# DDB_Power_Supply.net
KiCad netlist of a schematic drawn in EAGLE
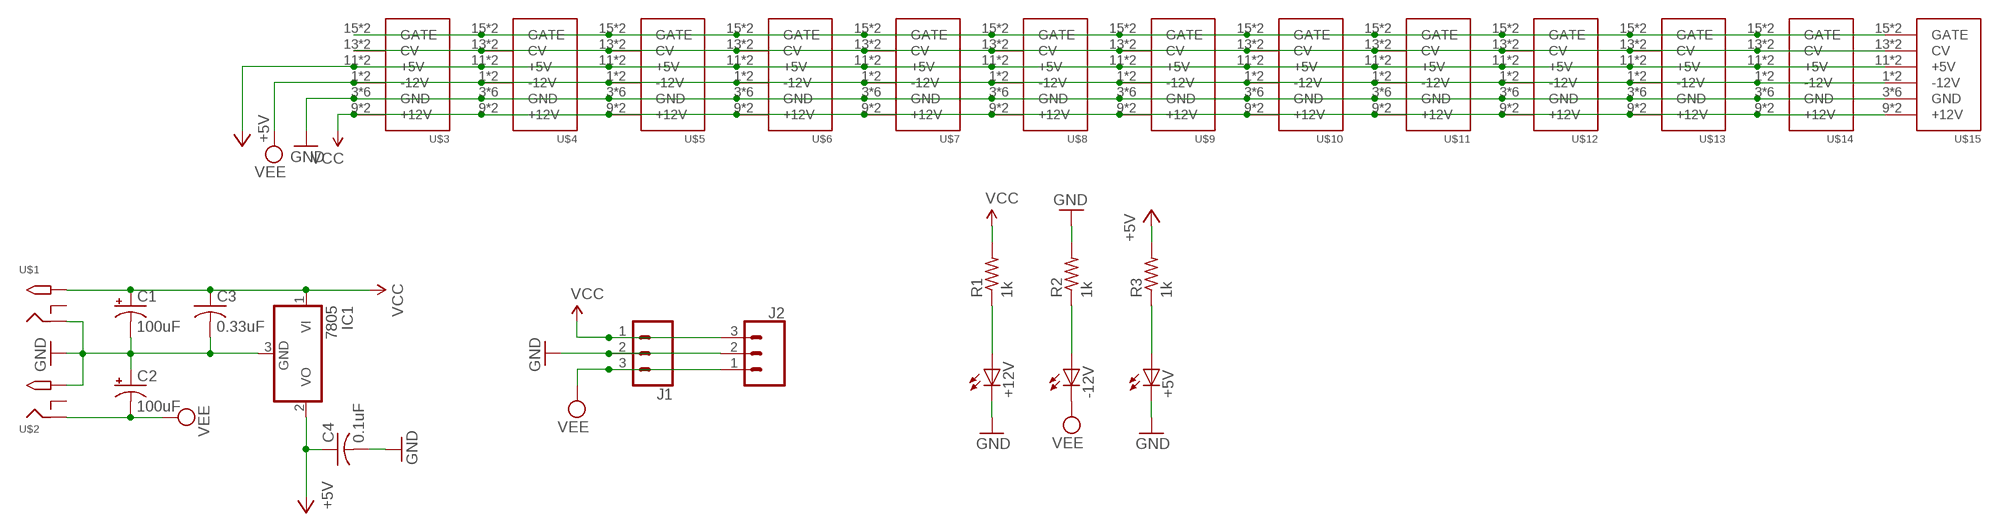
[diagram p0: schematic, sheet 1]

(export (version "E")
  (design (tool "Eeschema 10.0.6"))
  (components
    (comp (ref "+5V")
      (value "LED3MM")
      (footprint "eagle-import:LED3MM")
      (libsource (lib "eagle-import") (part "LED3MM"))
    )
    (comp (ref "+12V")
      (value "LED3MM")
      (footprint "eagle-import:LED3MM")
      (libsource (lib "eagle-import") (part "LED3MM"))
    )
    (comp (ref "-12V")
      (value "LED3MM")
      (footprint "eagle-import:LED3MM")
      (libsource (lib "eagle-import") (part "LED3MM"))
    )
    (comp (ref "C1")
      (value "100uF")
      (footprint "eagle-import:E3,5-8")
      (libsource (lib "eagle-import") (part "CPOL-USE3.5-8"))
    )
    (comp (ref "C2")
      (value "100uF")
      (footprint "eagle-import:E3,5-8")
      (libsource (lib "eagle-import") (part "CPOL-USE3.5-8"))
    )
    (comp (ref "C3")
      (value "0.33uF")
      (footprint "eagle-import:C0805")
      (libsource (lib "eagle-import") (part "C-USC0805"))
    )
    (comp (ref "C4")
      (value "0.1uF")
      (footprint "eagle-import:C0805")
      (libsource (lib "eagle-import") (part "C-USC0805"))
    )
    (comp (ref "IC1")
      (value "7805")
      (footprint "eagle-import:TO252")
      (libsource (lib "eagle-import") (part "78DT24"))
    )
    (comp (ref "J1")
      (value "CONN_03SCREW")
      (footprint "eagle-import:SCREWTERMINAL-3.5MM-3")
      (libsource (lib "eagle-import") (part "CONN_03SCREW"))
    )
    (comp (ref "J2")
      (value "CONN_03SCREW")
      (footprint "eagle-import:SCREWTERMINAL-3.5MM-3")
      (libsource (lib "eagle-import") (part "CONN_03SCREW"))
    )
    (comp (ref "R1")
      (value "1k")
      (footprint "eagle-import:R0805")
      (libsource (lib "eagle-import") (part "R-US_R0805"))
    )
    (comp (ref "R2")
      (value "1k")
      (footprint "eagle-import:R0805")
      (libsource (lib "eagle-import") (part "R-US_R0805"))
    )
    (comp (ref "R3")
      (value "1k")
      (footprint "eagle-import:R0805")
      (libsource (lib "eagle-import") (part "R-US_R0805"))
    )
    (comp (ref "U$1")
      (value "2.1MMJACKTHM")
      (footprint "eagle-import:PJ-102A")
      (libsource (lib "eagle-import") (part "2.1MMJACKTHM"))
    )
    (comp (ref "U$2")
      (value "2.1MMJACKTHM")
      (footprint "eagle-import:PJ-102A")
      (libsource (lib "eagle-import") (part "2.1MMJACKTHM"))
    )
    (comp (ref "U$3")
      (value "POWER")
      (footprint "eagle-import:POWER_16")
      (libsource (lib "eagle-import") (part "POWER"))
    )
    (comp (ref "U$4")
      (value "POWER")
      (footprint "eagle-import:POWER_16")
      (libsource (lib "eagle-import") (part "POWER"))
    )
    (comp (ref "U$5")
      (value "POWER")
      (footprint "eagle-import:POWER_16")
      (libsource (lib "eagle-import") (part "POWER"))
    )
    (comp (ref "U$6")
      (value "POWER")
      (footprint "eagle-import:POWER_16")
      (libsource (lib "eagle-import") (part "POWER"))
    )
    (comp (ref "U$7")
      (value "POWER")
      (footprint "eagle-import:POWER_16")
      (libsource (lib "eagle-import") (part "POWER"))
    )
    (comp (ref "U$8")
      (value "POWER")
      (footprint "eagle-import:POWER_16")
      (libsource (lib "eagle-import") (part "POWER"))
    )
    (comp (ref "U$9")
      (value "POWER")
      (footprint "eagle-import:POWER_16")
      (libsource (lib "eagle-import") (part "POWER"))
    )
    (comp (ref "U$10")
      (value "POWER")
      (footprint "eagle-import:POWER_16")
      (libsource (lib "eagle-import") (part "POWER"))
    )
    (comp (ref "U$11")
      (value "POWER")
      (footprint "eagle-import:POWER_16")
      (libsource (lib "eagle-import") (part "POWER"))
    )
    (comp (ref "U$12")
      (value "POWER")
      (footprint "eagle-import:POWER_16")
      (libsource (lib "eagle-import") (part "POWER"))
    )
    (comp (ref "U$13")
      (value "POWER")
      (footprint "eagle-import:POWER_16")
      (libsource (lib "eagle-import") (part "POWER"))
    )
    (comp (ref "U$14")
      (value "POWER")
      (footprint "eagle-import:POWER_16")
      (libsource (lib "eagle-import") (part "POWER"))
    )
    (comp (ref "U$15")
      (value "POWER")
      (footprint "eagle-import:POWER_16")
      (libsource (lib "eagle-import") (part "POWER"))
    )
  )
  (nets
    (net (code "1") (name "+5V") (class "Default")
      (node (ref "C4") (pin "1") (pinfunction "1_1") (pintype "passive"))
      (node (ref "IC1") (pin "2") (pinfunction "VO_2") (pintype "passive"))
      (node (ref "R3") (pin "2") (pinfunction "2_2") (pintype "passive"))
      (node (ref "U$10") (pin "11") (pinfunction "+5V_11") (pintype "bidirectional"))
      (node (ref "U$10") (pin "12") (pinfunction "+5V_12") (pintype "bidirectional"))
      (node (ref "U$11") (pin "11") (pinfunction "+5V_11") (pintype "bidirectional"))
      (node (ref "U$11") (pin "12") (pinfunction "+5V_12") (pintype "bidirectional"))
      (node (ref "U$12") (pin "11") (pinfunction "+5V_11") (pintype "bidirectional"))
      (node (ref "U$12") (pin "12") (pinfunction "+5V_12") (pintype "bidirectional"))
      (node (ref "U$13") (pin "11") (pinfunction "+5V_11") (pintype "bidirectional"))
      (node (ref "U$13") (pin "12") (pinfunction "+5V_12") (pintype "bidirectional"))
      (node (ref "U$14") (pin "11") (pinfunction "+5V_11") (pintype "bidirectional"))
      (node (ref "U$14") (pin "12") (pinfunction "+5V_12") (pintype "bidirectional"))
      (node (ref "U$15") (pin "11") (pinfunction "+5V_11") (pintype "bidirectional"))
      (node (ref "U$15") (pin "12") (pinfunction "+5V_12") (pintype "bidirectional"))
      (node (ref "U$3") (pin "11") (pinfunction "+5V_11") (pintype "bidirectional"))
      (node (ref "U$3") (pin "12") (pinfunction "+5V_12") (pintype "bidirectional"))
      (node (ref "U$4") (pin "11") (pinfunction "+5V_11") (pintype "bidirectional"))
      (node (ref "U$4") (pin "12") (pinfunction "+5V_12") (pintype "bidirectional"))
      (node (ref "U$5") (pin "11") (pinfunction "+5V_11") (pintype "bidirectional"))
      (node (ref "U$5") (pin "12") (pinfunction "+5V_12") (pintype "bidirectional"))
      (node (ref "U$6") (pin "11") (pinfunction "+5V_11") (pintype "bidirectional"))
      (node (ref "U$6") (pin "12") (pinfunction "+5V_12") (pintype "bidirectional"))
      (node (ref "U$7") (pin "11") (pinfunction "+5V_11") (pintype "bidirectional"))
      (node (ref "U$7") (pin "12") (pinfunction "+5V_12") (pintype "bidirectional"))
      (node (ref "U$8") (pin "11") (pinfunction "+5V_11") (pintype "bidirectional"))
      (node (ref "U$8") (pin "12") (pinfunction "+5V_12") (pintype "bidirectional"))
      (node (ref "U$9") (pin "11") (pinfunction "+5V_11") (pintype "bidirectional"))
      (node (ref "U$9") (pin "12") (pinfunction "+5V_12") (pintype "bidirectional"))
    )
    (net (code "2") (name "GND") (class "Default")
      (node (ref "+12V") (pin "K") (pinfunction "C_K") (pintype "passive"))
      (node (ref "+5V") (pin "K") (pinfunction "C_K") (pintype "passive"))
      (node (ref "C1") (pin "-") (pinfunction "-_-") (pintype "passive"))
      (node (ref "C2") (pin "+") (pinfunction "+_+") (pintype "passive"))
      (node (ref "C3") (pin "2") (pinfunction "2_2") (pintype "passive"))
      (node (ref "C4") (pin "2") (pinfunction "2_2") (pintype "passive"))
      (node (ref "IC1") (pin "3") (pinfunction "GND_3") (pintype "passive"))
      (node (ref "J1") (pin "2") (pinfunction "2_2") (pintype "passive"))
      (node (ref "J2") (pin "2") (pinfunction "2_2") (pintype "passive"))
      (node (ref "R2") (pin "2") (pinfunction "2_2") (pintype "passive"))
      (node (ref "U$1") (pin "RING") (pinfunction "RING_RING") (pintype "bidirectional"))
      (node (ref "U$10") (pin "3") (pinfunction "GND_3") (pintype "bidirectional"))
      (node (ref "U$10") (pin "4") (pinfunction "GND_4") (pintype "bidirectional"))
      (node (ref "U$10") (pin "5") (pinfunction "GND_5") (pintype "bidirectional"))
      (node (ref "U$10") (pin "6") (pinfunction "GND_6") (pintype "bidirectional"))
      (node (ref "U$10") (pin "7") (pinfunction "GND_7") (pintype "bidirectional"))
      (node (ref "U$10") (pin "8") (pinfunction "GND_8") (pintype "bidirectional"))
      (node (ref "U$11") (pin "3") (pinfunction "GND_3") (pintype "bidirectional"))
      (node (ref "U$11") (pin "4") (pinfunction "GND_4") (pintype "bidirectional"))
      (node (ref "U$11") (pin "5") (pinfunction "GND_5") (pintype "bidirectional"))
      (node (ref "U$11") (pin "6") (pinfunction "GND_6") (pintype "bidirectional"))
      (node (ref "U$11") (pin "7") (pinfunction "GND_7") (pintype "bidirectional"))
      (node (ref "U$11") (pin "8") (pinfunction "GND_8") (pintype "bidirectional"))
      (node (ref "U$12") (pin "3") (pinfunction "GND_3") (pintype "bidirectional"))
      (node (ref "U$12") (pin "4") (pinfunction "GND_4") (pintype "bidirectional"))
      (node (ref "U$12") (pin "5") (pinfunction "GND_5") (pintype "bidirectional"))
      (node (ref "U$12") (pin "6") (pinfunction "GND_6") (pintype "bidirectional"))
      (node (ref "U$12") (pin "7") (pinfunction "GND_7") (pintype "bidirectional"))
      (node (ref "U$12") (pin "8") (pinfunction "GND_8") (pintype "bidirectional"))
      (node (ref "U$13") (pin "3") (pinfunction "GND_3") (pintype "bidirectional"))
      (node (ref "U$13") (pin "4") (pinfunction "GND_4") (pintype "bidirectional"))
      (node (ref "U$13") (pin "5") (pinfunction "GND_5") (pintype "bidirectional"))
      (node (ref "U$13") (pin "6") (pinfunction "GND_6") (pintype "bidirectional"))
      (node (ref "U$13") (pin "7") (pinfunction "GND_7") (pintype "bidirectional"))
      (node (ref "U$13") (pin "8") (pinfunction "GND_8") (pintype "bidirectional"))
      (node (ref "U$14") (pin "3") (pinfunction "GND_3") (pintype "bidirectional"))
      (node (ref "U$14") (pin "4") (pinfunction "GND_4") (pintype "bidirectional"))
      (node (ref "U$14") (pin "5") (pinfunction "GND_5") (pintype "bidirectional"))
      (node (ref "U$14") (pin "6") (pinfunction "GND_6") (pintype "bidirectional"))
      (node (ref "U$14") (pin "7") (pinfunction "GND_7") (pintype "bidirectional"))
      (node (ref "U$14") (pin "8") (pinfunction "GND_8") (pintype "bidirectional"))
      (node (ref "U$15") (pin "3") (pinfunction "GND_3") (pintype "bidirectional"))
      (node (ref "U$15") (pin "4") (pinfunction "GND_4") (pintype "bidirectional"))
      (node (ref "U$15") (pin "5") (pinfunction "GND_5") (pintype "bidirectional"))
      (node (ref "U$15") (pin "6") (pinfunction "GND_6") (pintype "bidirectional"))
      (node (ref "U$15") (pin "7") (pinfunction "GND_7") (pintype "bidirectional"))
      (node (ref "U$15") (pin "8") (pinfunction "GND_8") (pintype "bidirectional"))
      (node (ref "U$2") (pin "TIP") (pinfunction "TIP_TIP") (pintype "bidirectional"))
      (node (ref "U$3") (pin "3") (pinfunction "GND_3") (pintype "bidirectional"))
      (node (ref "U$3") (pin "4") (pinfunction "GND_4") (pintype "bidirectional"))
      (node (ref "U$3") (pin "5") (pinfunction "GND_5") (pintype "bidirectional"))
      (node (ref "U$3") (pin "6") (pinfunction "GND_6") (pintype "bidirectional"))
      (node (ref "U$3") (pin "7") (pinfunction "GND_7") (pintype "bidirectional"))
      (node (ref "U$3") (pin "8") (pinfunction "GND_8") (pintype "bidirectional"))
      (node (ref "U$4") (pin "3") (pinfunction "GND_3") (pintype "bidirectional"))
      (node (ref "U$4") (pin "4") (pinfunction "GND_4") (pintype "bidirectional"))
      (node (ref "U$4") (pin "5") (pinfunction "GND_5") (pintype "bidirectional"))
      (node (ref "U$4") (pin "6") (pinfunction "GND_6") (pintype "bidirectional"))
      (node (ref "U$4") (pin "7") (pinfunction "GND_7") (pintype "bidirectional"))
      (node (ref "U$4") (pin "8") (pinfunction "GND_8") (pintype "bidirectional"))
      (node (ref "U$5") (pin "3") (pinfunction "GND_3") (pintype "bidirectional"))
      (node (ref "U$5") (pin "4") (pinfunction "GND_4") (pintype "bidirectional"))
      (node (ref "U$5") (pin "5") (pinfunction "GND_5") (pintype "bidirectional"))
      (node (ref "U$5") (pin "6") (pinfunction "GND_6") (pintype "bidirectional"))
      (node (ref "U$5") (pin "7") (pinfunction "GND_7") (pintype "bidirectional"))
      (node (ref "U$5") (pin "8") (pinfunction "GND_8") (pintype "bidirectional"))
      (node (ref "U$6") (pin "3") (pinfunction "GND_3") (pintype "bidirectional"))
      (node (ref "U$6") (pin "4") (pinfunction "GND_4") (pintype "bidirectional"))
      (node (ref "U$6") (pin "5") (pinfunction "GND_5") (pintype "bidirectional"))
      (node (ref "U$6") (pin "6") (pinfunction "GND_6") (pintype "bidirectional"))
      (node (ref "U$6") (pin "7") (pinfunction "GND_7") (pintype "bidirectional"))
      (node (ref "U$6") (pin "8") (pinfunction "GND_8") (pintype "bidirectional"))
      (node (ref "U$7") (pin "3") (pinfunction "GND_3") (pintype "bidirectional"))
      (node (ref "U$7") (pin "4") (pinfunction "GND_4") (pintype "bidirectional"))
      (node (ref "U$7") (pin "5") (pinfunction "GND_5") (pintype "bidirectional"))
      (node (ref "U$7") (pin "6") (pinfunction "GND_6") (pintype "bidirectional"))
      (node (ref "U$7") (pin "7") (pinfunction "GND_7") (pintype "bidirectional"))
      (node (ref "U$7") (pin "8") (pinfunction "GND_8") (pintype "bidirectional"))
      (node (ref "U$8") (pin "3") (pinfunction "GND_3") (pintype "bidirectional"))
      (node (ref "U$8") (pin "4") (pinfunction "GND_4") (pintype "bidirectional"))
      (node (ref "U$8") (pin "5") (pinfunction "GND_5") (pintype "bidirectional"))
      (node (ref "U$8") (pin "6") (pinfunction "GND_6") (pintype "bidirectional"))
      (node (ref "U$8") (pin "7") (pinfunction "GND_7") (pintype "bidirectional"))
      (node (ref "U$8") (pin "8") (pinfunction "GND_8") (pintype "bidirectional"))
      (node (ref "U$9") (pin "3") (pinfunction "GND_3") (pintype "bidirectional"))
      (node (ref "U$9") (pin "4") (pinfunction "GND_4") (pintype "bidirectional"))
      (node (ref "U$9") (pin "5") (pinfunction "GND_5") (pintype "bidirectional"))
      (node (ref "U$9") (pin "6") (pinfunction "GND_6") (pintype "bidirectional"))
      (node (ref "U$9") (pin "7") (pinfunction "GND_7") (pintype "bidirectional"))
      (node (ref "U$9") (pin "8") (pinfunction "GND_8") (pintype "bidirectional"))
    )
    (net (code "3") (name "Net-(+5V-PadA)") (class "Default")
      (node (ref "+5V") (pin "A") (pinfunction "A_A") (pintype "passive"))
      (node (ref "R3") (pin "1") (pinfunction "1_1") (pintype "passive"))
    )
    (net (code "4") (name "Net-(+12V-PadA)") (class "Default")
      (node (ref "+12V") (pin "A") (pinfunction "A_A") (pintype "passive"))
      (node (ref "R1") (pin "1") (pinfunction "1_1") (pintype "passive"))
    )
    (net (code "5") (name "Net-(-12V-PadA)") (class "Default")
      (node (ref "-12V") (pin "A") (pinfunction "A_A") (pintype "passive"))
      (node (ref "R2") (pin "1") (pinfunction "1_1") (pintype "passive"))
    )
    (net (code "6") (name "Net-(U$10-CV-Pad13)") (class "Default")
      (node (ref "U$10") (pin "13") (pinfunction "CV_13") (pintype "bidirectional"))
      (node (ref "U$10") (pin "14") (pinfunction "CV_14") (pintype "bidirectional"))
      (node (ref "U$11") (pin "13") (pinfunction "CV_13") (pintype "bidirectional"))
      (node (ref "U$11") (pin "14") (pinfunction "CV_14") (pintype "bidirectional"))
      (node (ref "U$12") (pin "13") (pinfunction "CV_13") (pintype "bidirectional"))
      (node (ref "U$12") (pin "14") (pinfunction "CV_14") (pintype "bidirectional"))
      (node (ref "U$13") (pin "13") (pinfunction "CV_13") (pintype "bidirectional"))
      (node (ref "U$13") (pin "14") (pinfunction "CV_14") (pintype "bidirectional"))
      (node (ref "U$14") (pin "13") (pinfunction "CV_13") (pintype "bidirectional"))
      (node (ref "U$14") (pin "14") (pinfunction "CV_14") (pintype "bidirectional"))
      (node (ref "U$15") (pin "13") (pinfunction "CV_13") (pintype "bidirectional"))
      (node (ref "U$15") (pin "14") (pinfunction "CV_14") (pintype "bidirectional"))
      (node (ref "U$3") (pin "13") (pinfunction "CV_13") (pintype "bidirectional"))
      (node (ref "U$3") (pin "14") (pinfunction "CV_14") (pintype "bidirectional"))
      (node (ref "U$4") (pin "13") (pinfunction "CV_13") (pintype "bidirectional"))
      (node (ref "U$4") (pin "14") (pinfunction "CV_14") (pintype "bidirectional"))
      (node (ref "U$5") (pin "13") (pinfunction "CV_13") (pintype "bidirectional"))
      (node (ref "U$5") (pin "14") (pinfunction "CV_14") (pintype "bidirectional"))
      (node (ref "U$6") (pin "13") (pinfunction "CV_13") (pintype "bidirectional"))
      (node (ref "U$6") (pin "14") (pinfunction "CV_14") (pintype "bidirectional"))
      (node (ref "U$7") (pin "13") (pinfunction "CV_13") (pintype "bidirectional"))
      (node (ref "U$7") (pin "14") (pinfunction "CV_14") (pintype "bidirectional"))
      (node (ref "U$8") (pin "13") (pinfunction "CV_13") (pintype "bidirectional"))
      (node (ref "U$8") (pin "14") (pinfunction "CV_14") (pintype "bidirectional"))
      (node (ref "U$9") (pin "13") (pinfunction "CV_13") (pintype "bidirectional"))
      (node (ref "U$9") (pin "14") (pinfunction "CV_14") (pintype "bidirectional"))
    )
    (net (code "7") (name "Net-(U$10-GATE-Pad15)") (class "Default")
      (node (ref "U$10") (pin "15") (pinfunction "GATE_15") (pintype "bidirectional"))
      (node (ref "U$10") (pin "16") (pinfunction "GATE_16") (pintype "bidirectional"))
      (node (ref "U$11") (pin "15") (pinfunction "GATE_15") (pintype "bidirectional"))
      (node (ref "U$11") (pin "16") (pinfunction "GATE_16") (pintype "bidirectional"))
      (node (ref "U$12") (pin "15") (pinfunction "GATE_15") (pintype "bidirectional"))
      (node (ref "U$12") (pin "16") (pinfunction "GATE_16") (pintype "bidirectional"))
      (node (ref "U$13") (pin "15") (pinfunction "GATE_15") (pintype "bidirectional"))
      (node (ref "U$13") (pin "16") (pinfunction "GATE_16") (pintype "bidirectional"))
      (node (ref "U$14") (pin "15") (pinfunction "GATE_15") (pintype "bidirectional"))
      (node (ref "U$14") (pin "16") (pinfunction "GATE_16") (pintype "bidirectional"))
      (node (ref "U$15") (pin "15") (pinfunction "GATE_15") (pintype "bidirectional"))
      (node (ref "U$15") (pin "16") (pinfunction "GATE_16") (pintype "bidirectional"))
      (node (ref "U$3") (pin "15") (pinfunction "GATE_15") (pintype "bidirectional"))
      (node (ref "U$3") (pin "16") (pinfunction "GATE_16") (pintype "bidirectional"))
      (node (ref "U$4") (pin "15") (pinfunction "GATE_15") (pintype "bidirectional"))
      (node (ref "U$4") (pin "16") (pinfunction "GATE_16") (pintype "bidirectional"))
      (node (ref "U$5") (pin "15") (pinfunction "GATE_15") (pintype "bidirectional"))
      (node (ref "U$5") (pin "16") (pinfunction "GATE_16") (pintype "bidirectional"))
      (node (ref "U$6") (pin "15") (pinfunction "GATE_15") (pintype "bidirectional"))
      (node (ref "U$6") (pin "16") (pinfunction "GATE_16") (pintype "bidirectional"))
      (node (ref "U$7") (pin "15") (pinfunction "GATE_15") (pintype "bidirectional"))
      (node (ref "U$7") (pin "16") (pinfunction "GATE_16") (pintype "bidirectional"))
      (node (ref "U$8") (pin "15") (pinfunction "GATE_15") (pintype "bidirectional"))
      (node (ref "U$8") (pin "16") (pinfunction "GATE_16") (pintype "bidirectional"))
      (node (ref "U$9") (pin "15") (pinfunction "GATE_15") (pintype "bidirectional"))
      (node (ref "U$9") (pin "16") (pinfunction "GATE_16") (pintype "bidirectional"))
    )
    (net (code "8") (name "VCC") (class "Default")
      (node (ref "C1") (pin "+") (pinfunction "+_+") (pintype "passive"))
      (node (ref "C3") (pin "1") (pinfunction "1_1") (pintype "passive"))
      (node (ref "IC1") (pin "1") (pinfunction "VI_1") (pintype "input"))
      (node (ref "J1") (pin "1") (pinfunction "1_1") (pintype "passive"))
      (node (ref "J2") (pin "3") (pinfunction "3_3") (pintype "passive"))
      (node (ref "R1") (pin "2") (pinfunction "2_2") (pintype "passive"))
      (node (ref "U$1") (pin "TIP") (pinfunction "TIP_TIP") (pintype "bidirectional"))
      (node (ref "U$10") (pin "10") (pinfunction "+12V_10") (pintype "bidirectional"))
      (node (ref "U$10") (pin "9") (pinfunction "+12V_9") (pintype "bidirectional"))
      (node (ref "U$11") (pin "10") (pinfunction "+12V_10") (pintype "bidirectional"))
      (node (ref "U$11") (pin "9") (pinfunction "+12V_9") (pintype "bidirectional"))
      (node (ref "U$12") (pin "10") (pinfunction "+12V_10") (pintype "bidirectional"))
      (node (ref "U$12") (pin "9") (pinfunction "+12V_9") (pintype "bidirectional"))
      (node (ref "U$13") (pin "10") (pinfunction "+12V_10") (pintype "bidirectional"))
      (node (ref "U$13") (pin "9") (pinfunction "+12V_9") (pintype "bidirectional"))
      (node (ref "U$14") (pin "10") (pinfunction "+12V_10") (pintype "bidirectional"))
      (node (ref "U$14") (pin "9") (pinfunction "+12V_9") (pintype "bidirectional"))
      (node (ref "U$15") (pin "10") (pinfunction "+12V_10") (pintype "bidirectional"))
      (node (ref "U$15") (pin "9") (pinfunction "+12V_9") (pintype "bidirectional"))
      (node (ref "U$3") (pin "10") (pinfunction "+12V_10") (pintype "bidirectional"))
      (node (ref "U$3") (pin "9") (pinfunction "+12V_9") (pintype "bidirectional"))
      (node (ref "U$4") (pin "10") (pinfunction "+12V_10") (pintype "bidirectional"))
      (node (ref "U$4") (pin "9") (pinfunction "+12V_9") (pintype "bidirectional"))
      (node (ref "U$5") (pin "10") (pinfunction "+12V_10") (pintype "bidirectional"))
      (node (ref "U$5") (pin "9") (pinfunction "+12V_9") (pintype "bidirectional"))
      (node (ref "U$6") (pin "10") (pinfunction "+12V_10") (pintype "bidirectional"))
      (node (ref "U$6") (pin "9") (pinfunction "+12V_9") (pintype "bidirectional"))
      (node (ref "U$7") (pin "10") (pinfunction "+12V_10") (pintype "bidirectional"))
      (node (ref "U$7") (pin "9") (pinfunction "+12V_9") (pintype "bidirectional"))
      (node (ref "U$8") (pin "10") (pinfunction "+12V_10") (pintype "bidirectional"))
      (node (ref "U$8") (pin "9") (pinfunction "+12V_9") (pintype "bidirectional"))
      (node (ref "U$9") (pin "10") (pinfunction "+12V_10") (pintype "bidirectional"))
      (node (ref "U$9") (pin "9") (pinfunction "+12V_9") (pintype "bidirectional"))
    )
    (net (code "9") (name "VEE") (class "Default")
      (node (ref "-12V") (pin "K") (pinfunction "C_K") (pintype "passive"))
      (node (ref "C2") (pin "-") (pinfunction "-_-") (pintype "passive"))
      (node (ref "J1") (pin "3") (pinfunction "3_3") (pintype "passive"))
      (node (ref "J2") (pin "1") (pinfunction "1_1") (pintype "passive"))
      (node (ref "U$10") (pin "1") (pinfunction "-12V_1") (pintype "bidirectional"))
      (node (ref "U$10") (pin "2") (pinfunction "-12V_2") (pintype "bidirectional"))
      (node (ref "U$11") (pin "1") (pinfunction "-12V_1") (pintype "bidirectional"))
      (node (ref "U$11") (pin "2") (pinfunction "-12V_2") (pintype "bidirectional"))
      (node (ref "U$12") (pin "1") (pinfunction "-12V_1") (pintype "bidirectional"))
      (node (ref "U$12") (pin "2") (pinfunction "-12V_2") (pintype "bidirectional"))
      (node (ref "U$13") (pin "1") (pinfunction "-12V_1") (pintype "bidirectional"))
      (node (ref "U$13") (pin "2") (pinfunction "-12V_2") (pintype "bidirectional"))
      (node (ref "U$14") (pin "1") (pinfunction "-12V_1") (pintype "bidirectional"))
      (node (ref "U$14") (pin "2") (pinfunction "-12V_2") (pintype "bidirectional"))
      (node (ref "U$15") (pin "1") (pinfunction "-12V_1") (pintype "bidirectional"))
      (node (ref "U$15") (pin "2") (pinfunction "-12V_2") (pintype "bidirectional"))
      (node (ref "U$2") (pin "RING") (pinfunction "RING_RING") (pintype "bidirectional"))
      (node (ref "U$3") (pin "1") (pinfunction "-12V_1") (pintype "bidirectional"))
      (node (ref "U$3") (pin "2") (pinfunction "-12V_2") (pintype "bidirectional"))
      (node (ref "U$4") (pin "1") (pinfunction "-12V_1") (pintype "bidirectional"))
      (node (ref "U$4") (pin "2") (pinfunction "-12V_2") (pintype "bidirectional"))
      (node (ref "U$5") (pin "1") (pinfunction "-12V_1") (pintype "bidirectional"))
      (node (ref "U$5") (pin "2") (pinfunction "-12V_2") (pintype "bidirectional"))
      (node (ref "U$6") (pin "1") (pinfunction "-12V_1") (pintype "bidirectional"))
      (node (ref "U$6") (pin "2") (pinfunction "-12V_2") (pintype "bidirectional"))
      (node (ref "U$7") (pin "1") (pinfunction "-12V_1") (pintype "bidirectional"))
      (node (ref "U$7") (pin "2") (pinfunction "-12V_2") (pintype "bidirectional"))
      (node (ref "U$8") (pin "1") (pinfunction "-12V_1") (pintype "bidirectional"))
      (node (ref "U$8") (pin "2") (pinfunction "-12V_2") (pintype "bidirectional"))
      (node (ref "U$9") (pin "1") (pinfunction "-12V_1") (pintype "bidirectional"))
      (node (ref "U$9") (pin "2") (pinfunction "-12V_2") (pintype "bidirectional"))
    )
    (net (code "10") (name "unconnected-(U$1-PadRING_SW)") (class "Default")
      (node (ref "U$1") (pin "RING_SW") (pinfunction "RING_SW_RING_SW") (pintype "bidirectional"))
    )
    (net (code "11") (name "unconnected-(U$2-PadRING_SW)") (class "Default")
      (node (ref "U$2") (pin "RING_SW") (pinfunction "RING_SW_RING_SW") (pintype "bidirectional"))
    )
  )
)
